# 18_ETH.net
KiCad netlist of a schematic drawn in Altium Designer
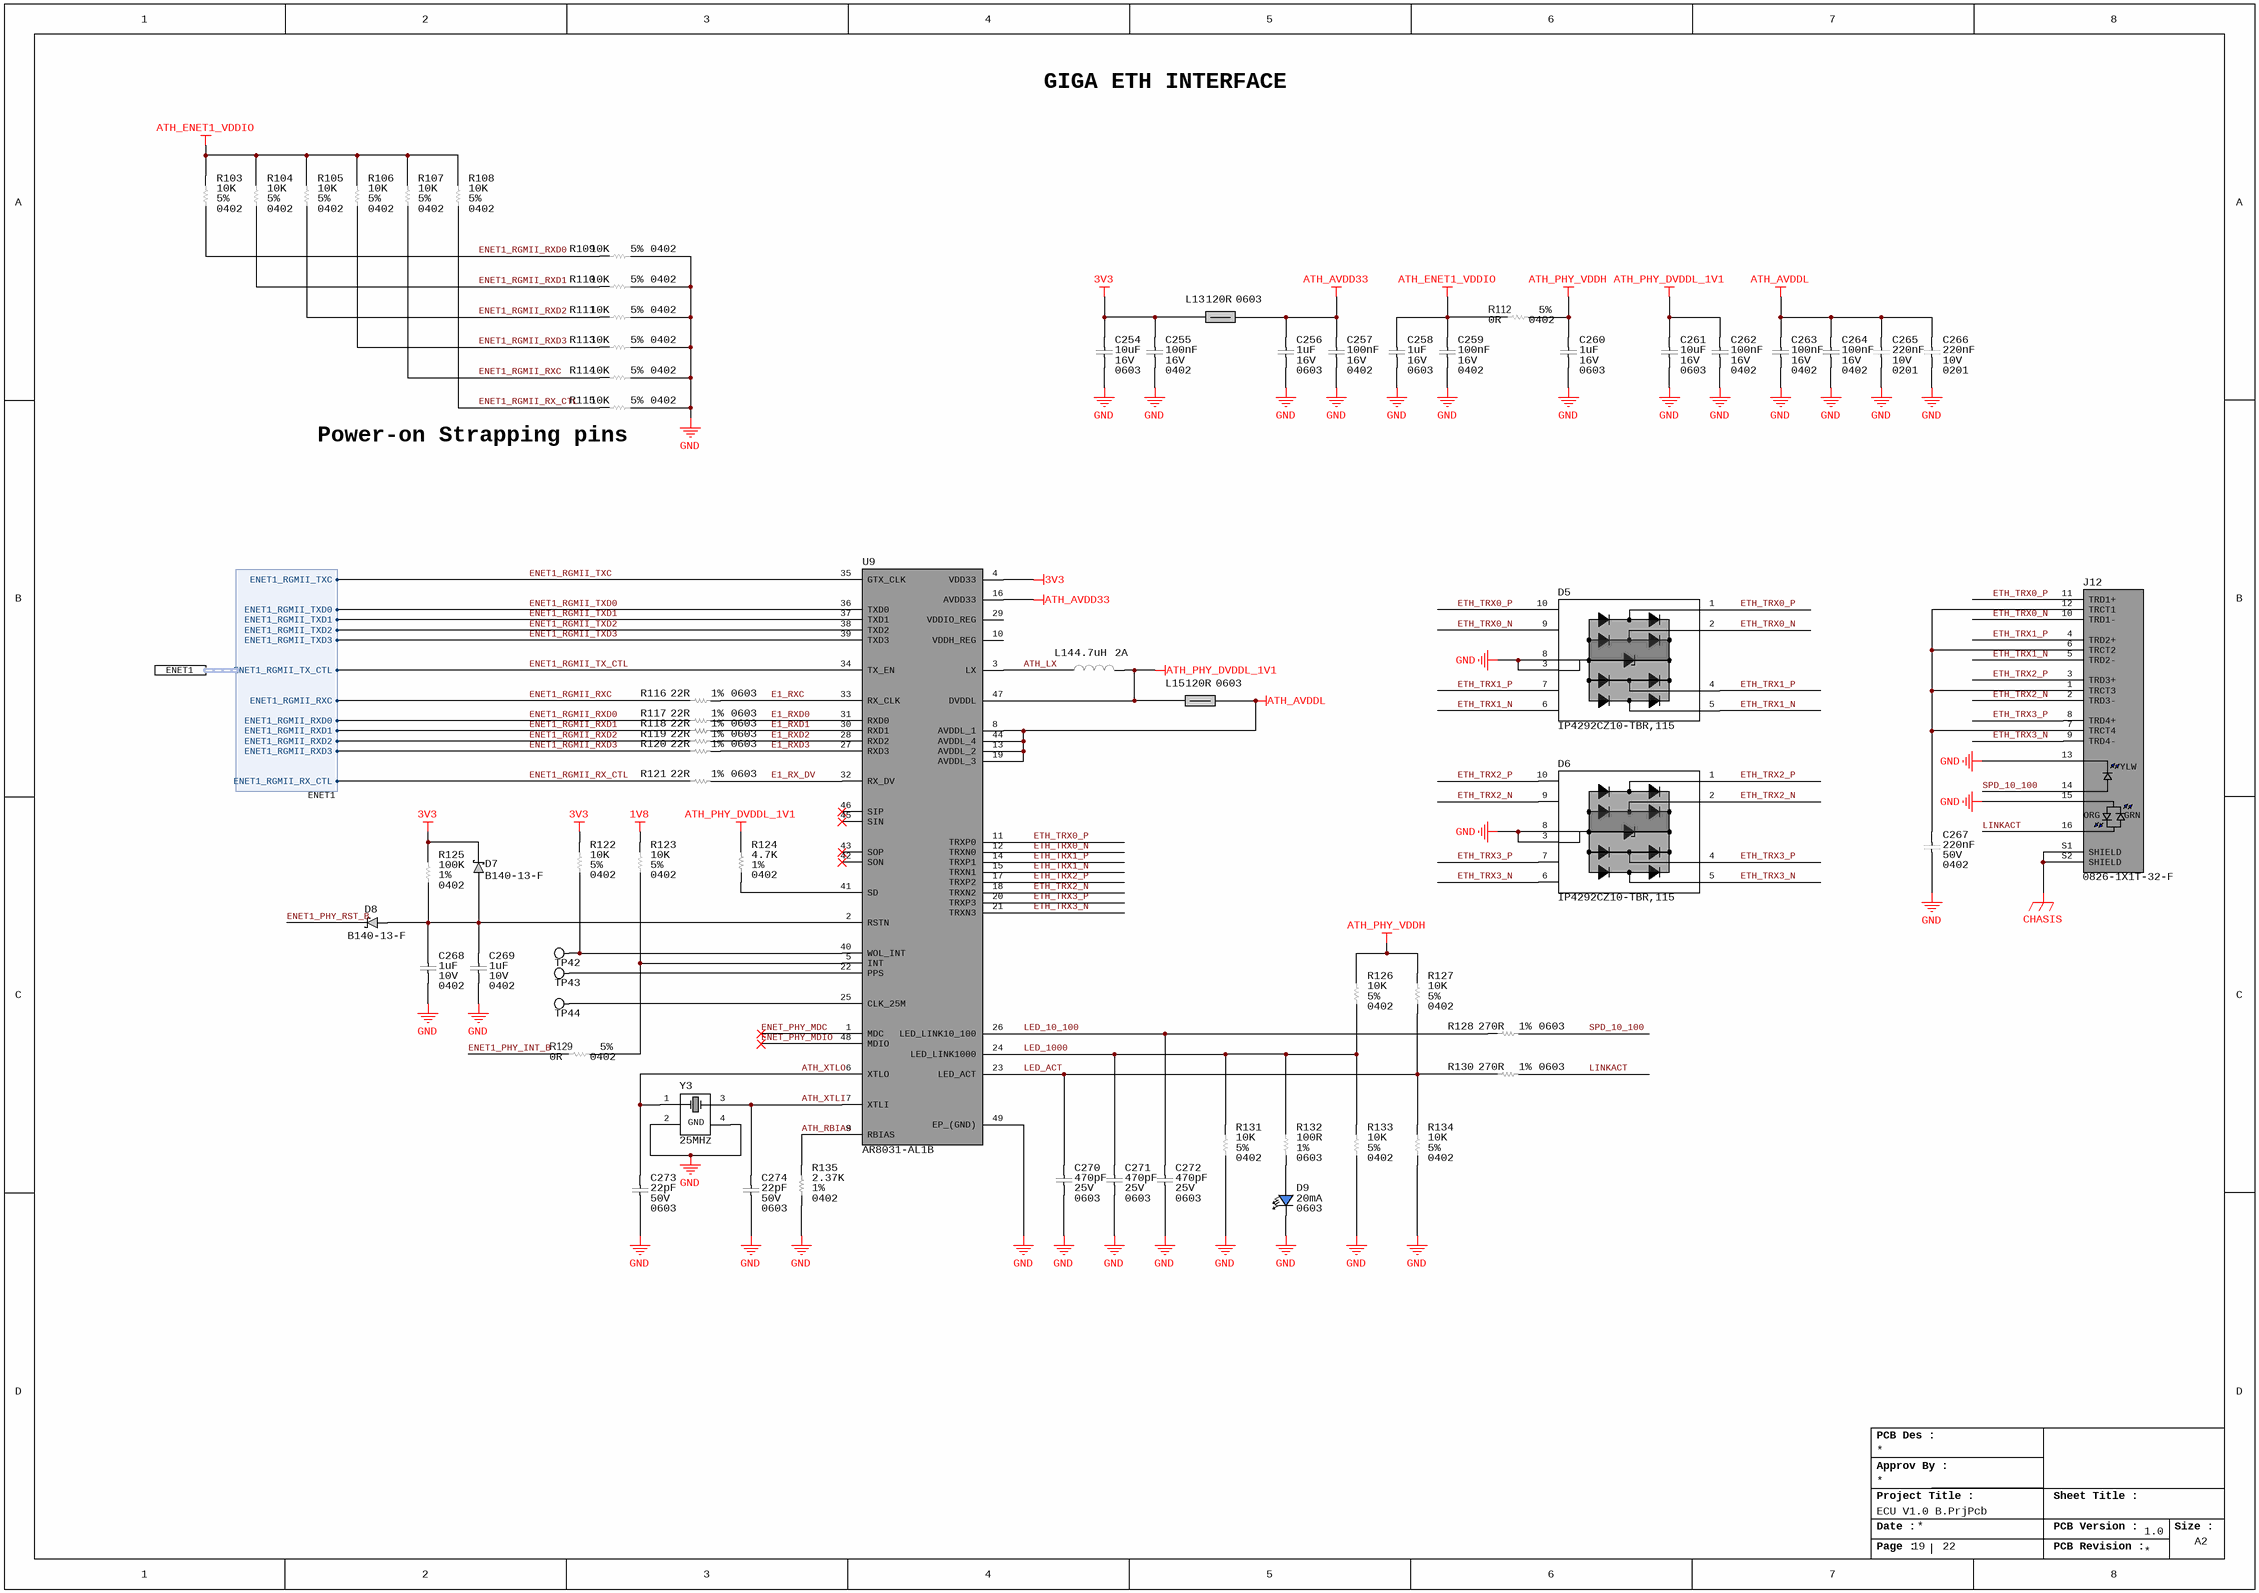
[diagram p0: 18_ETH.SchDoc]

(export (version "E")
  (design (tool "Eeschema 10.0.6"))
  (components
    (comp (ref "C254")
      (value "GRM188R61C106MAALD")
      (footprint "CAP_0603_CAPC1608X08N")
      (description "0603 10 uF 16 V ±20% Tolerance X5R Multilayer Ceramic Chip Capacitor")
      (fields
        (field (name "MANUFACTURER") "Murata")
        (field (name "TOLERANCE") "20%")
        (field (name "VOLTAGE RATING") "16V")
        (field (name "CAPACITANCE") "10uF")
        (field (name "CASE/PACKAGE") "0603")
      )
      (libsource (lib "Electronic Devices_LIB") (part "CAP_10UF_16V_X5R_0603"))
    )
    (comp (ref "C255")
      (value "CL05B104KO5NNNC")
      (footprint "CAP_0402_CAPC1005X05N")
      (description "Multilayer Ceramic Capacitor, 0.1 uF, 16 V, ± 10%, X7R, 0402 [1005 Metric]")
      (fields
        (field (name "MANUFACTURER") "Samsung")
        (field (name "TOLERANCE") "10%")
        (field (name "VOLTAGE RATING") "16V")
        (field (name "CAPACITANCE") "100nF")
        (field (name "CASE/PACKAGE") "0402")
      )
      (libsource (lib "Electronic Devices_LIB") (part "CAP_100NF_16V_X7R_0402"))
    )
    (comp (ref "C256")
      (value "CL10A105KO8NNNC")
      (footprint "CAP_0603_CAPC1608X08N")
      (description "CAP CER 1UF 16V X5R 0603")
      (fields
        (field (name "MANUFACTURER") "Samsung")
        (field (name "TOLERANCE") "10%")
        (field (name "VOLTAGE RATING") "16V")
        (field (name "CAPACITANCE") "1uF")
        (field (name "CASE/PACKAGE") "0603")
      )
      (libsource (lib "Electronic Devices_LIB") (part "CAP_1UF_16V_X5R_0603"))
    )
    (comp (ref "C257")
      (value "CL05B104KO5NNNC")
      (footprint "CAP_0402_CAPC1005X05N")
      (description "Multilayer Ceramic Capacitor, 0.1 uF, 16 V, ± 10%, X7R, 0402 [1005 Metric]")
      (fields
        (field (name "MANUFACTURER") "Samsung")
        (field (name "TOLERANCE") "10%")
        (field (name "VOLTAGE RATING") "16V")
        (field (name "CAPACITANCE") "100nF")
        (field (name "CASE/PACKAGE") "0402")
      )
      (libsource (lib "Electronic Devices_LIB") (part "CAP_100NF_16V_X7R_0402"))
    )
    (comp (ref "C258")
      (value "CL10A105KO8NNNC")
      (footprint "CAP_0603_CAPC1608X08N")
      (description "CAP CER 1UF 16V X5R 0603")
      (fields
        (field (name "MANUFACTURER") "Samsung")
        (field (name "TOLERANCE") "10%")
        (field (name "VOLTAGE RATING") "16V")
        (field (name "CAPACITANCE") "1uF")
        (field (name "CASE/PACKAGE") "0603")
      )
      (libsource (lib "Electronic Devices_LIB") (part "CAP_1UF_16V_X5R_0603"))
    )
    (comp (ref "C259")
      (value "CL05B104KO5NNNC")
      (footprint "CAP_0402_CAPC1005X05N")
      (description "Multilayer Ceramic Capacitor, 0.1 uF, 16 V, ± 10%, X7R, 0402 [1005 Metric]")
      (fields
        (field (name "MANUFACTURER") "Samsung")
        (field (name "TOLERANCE") "10%")
        (field (name "VOLTAGE RATING") "16V")
        (field (name "CAPACITANCE") "100nF")
        (field (name "CASE/PACKAGE") "0402")
      )
      (libsource (lib "Electronic Devices_LIB") (part "CAP_100NF_16V_X7R_0402"))
    )
    (comp (ref "C260")
      (value "CL10A105KO8NNNC")
      (footprint "CAP_0603_CAPC1608X08N")
      (description "CAP CER 1UF 16V X5R 0603")
      (fields
        (field (name "MANUFACTURER") "Samsung")
        (field (name "TOLERANCE") "10%")
        (field (name "VOLTAGE RATING") "16V")
        (field (name "CAPACITANCE") "1uF")
        (field (name "CASE/PACKAGE") "0603")
      )
      (libsource (lib "Electronic Devices_LIB") (part "CAP_1UF_16V_X5R_0603"))
    )
    (comp (ref "C261")
      (value "GRM188R61C106MAALD")
      (footprint "CAP_0603_CAPC1608X08N")
      (description "0603 10 uF 16 V ±20% Tolerance X5R Multilayer Ceramic Chip Capacitor")
      (fields
        (field (name "MANUFACTURER") "Murata")
        (field (name "TOLERANCE") "20%")
        (field (name "VOLTAGE RATING") "16V")
        (field (name "CAPACITANCE") "10uF")
        (field (name "CASE/PACKAGE") "0603")
      )
      (libsource (lib "Electronic Devices_LIB") (part "CAP_10UF_16V_X5R_0603"))
    )
    (comp (ref "C262")
      (value "CL05B104KO5NNNC")
      (footprint "CAP_0402_CAPC1005X05N")
      (description "Multilayer Ceramic Capacitor, 0.1 uF, 16 V, ± 10%, X7R, 0402 [1005 Metric]")
      (fields
        (field (name "MANUFACTURER") "Samsung")
        (field (name "TOLERANCE") "10%")
        (field (name "VOLTAGE RATING") "16V")
        (field (name "CAPACITANCE") "100nF")
        (field (name "CASE/PACKAGE") "0402")
      )
      (libsource (lib "Electronic Devices_LIB") (part "CAP_100NF_16V_X7R_0402"))
    )
    (comp (ref "C263")
      (value "CL05B104KO5NNNC")
      (footprint "CAP_0402_CAPC1005X05N")
      (description "Multilayer Ceramic Capacitor, 0.1 uF, 16 V, ± 10%, X7R, 0402 [1005 Metric]")
      (fields
        (field (name "MANUFACTURER") "Samsung")
        (field (name "TOLERANCE") "10%")
        (field (name "VOLTAGE RATING") "16V")
        (field (name "CAPACITANCE") "100nF")
        (field (name "CASE/PACKAGE") "0402")
      )
      (libsource (lib "Electronic Devices_LIB") (part "CAP_100NF_16V_X7R_0402"))
    )
    (comp (ref "C264")
      (value "CL05B104KO5NNNC")
      (footprint "CAP_0402_CAPC1005X05N")
      (description "Multilayer Ceramic Capacitor, 0.1 uF, 16 V, ± 10%, X7R, 0402 [1005 Metric]")
      (fields
        (field (name "MANUFACTURER") "Samsung")
        (field (name "TOLERANCE") "10%")
        (field (name "VOLTAGE RATING") "16V")
        (field (name "CAPACITANCE") "100nF")
        (field (name "CASE/PACKAGE") "0402")
      )
      (libsource (lib "Electronic Devices_LIB") (part "CAP_100NF_16V_X7R_0402"))
    )
    (comp (ref "C265")
      (value "LMK063BJ224MP-F")
      (footprint "CAP_0201_CAPC0603X03N")
      (description "Multilayer Ceramic Capacitors (High dielectric type), 10V, 0.22 uF, ± 20 %, 0201, X5R, RoHS")
      (fields
        (field (name "MANUFACTURER") "Taiyo Yuden")
        (field (name "TOLERANCE") "20%")
        (field (name "VOLTAGE RATING (DC)") "10V")
        (field (name "CAPACITANCE") "220nF")
        (field (name "CASE/PACKAGE") "0201")
      )
      (libsource (lib "Electronic Devices_LIB") (part "CAP_0.22UF_10V_X5R_0201"))
    )
    (comp (ref "C266")
      (value "LMK063BJ224MP-F")
      (footprint "CAP_0201_CAPC0603X03N")
      (description "Multilayer Ceramic Capacitors (High dielectric type), 10V, 0.22 uF, ± 20 %, 0201, X5R, RoHS")
      (fields
        (field (name "MANUFACTURER") "Taiyo Yuden")
        (field (name "TOLERANCE") "20%")
        (field (name "VOLTAGE RATING (DC)") "10V")
        (field (name "CAPACITANCE") "220nF")
        (field (name "CASE/PACKAGE") "0201")
      )
      (libsource (lib "Electronic Devices_LIB") (part "CAP_0.22UF_10V_X5R_0201"))
    )
    (comp (ref "C267")
      (value "GRM155R61H224KE01W")
      (footprint "CAP_0402_CAPC1005X05N")
      (description "Multilayer Ceramic Capacitor, 0.22 uF, 50 VDC, ± 10%, X5R, 0402 [1005 Metric]")
      (fields
        (field (name "MANUFACTURER") "Murata")
        (field (name "CASE/PACKAGE") "0402")
        (field (name "VOLTAGE RATING (DC)") "50V")
        (field (name "CAPACITANCE") "220nF")
      )
      (libsource (lib "Electronic Devices_LIB") (part "CAP_0.22UF_50V_X5R_0402"))
    )
    (comp (ref "C268")
      (value "GRM155C81A105KA12D")
      (footprint "CAP_0402_CAPC1005X05N")
      (description "0402 10 V 1 uF ±10% Tolerance X6S Multilayer Ceramic Capacitor")
      (fields
        (field (name "MANUFACTURER") "Murata")
        (field (name "TOLERANCE") "10%")
        (field (name "VOLTAGE RATING") "10V")
        (field (name "CAPACITANCE") "1uF")
        (field (name "CASE/PACKAGE") "0402")
      )
      (libsource (lib "Electronic Devices_LIB") (part "CAP_1UF_10V_X6S_0402"))
    )
    (comp (ref "C269")
      (value "GRM155C81A105KA12D")
      (footprint "CAP_0402_CAPC1005X05N")
      (description "0402 10 V 1 uF ±10% Tolerance X6S Multilayer Ceramic Capacitor")
      (fields
        (field (name "MANUFACTURER") "Murata")
        (field (name "TOLERANCE") "10%")
        (field (name "VOLTAGE RATING") "10V")
        (field (name "CAPACITANCE") "1uF")
        (field (name "CASE/PACKAGE") "0402")
      )
      (libsource (lib "Electronic Devices_LIB") (part "CAP_1UF_10V_X6S_0402"))
    )
    (comp (ref "C270")
      (value "C0603C471K3RACTU")
      (footprint "CAP_0603_CAPC1608X08N")
      (fields
        (field (name "MANUFACTURER") "KEMET")
        (field (name "TOLERANCE") "10%")
        (field (name "VOLTAGE RATING") "25V")
        (field (name "CAPACITANCE") "470pF")
        (field (name "CASE CODE (IMPERIAL)") "0603")
      )
      (libsource (lib "Electronic Devices_LIB") (part "CAP_470pF_25V_X7R_0603"))
    )
    (comp (ref "C271")
      (value "C0603C471K3RACTU")
      (footprint "CAP_0603_CAPC1608X08N")
      (fields
        (field (name "MANUFACTURER") "KEMET")
        (field (name "TOLERANCE") "10%")
        (field (name "VOLTAGE RATING") "25V")
        (field (name "CAPACITANCE") "470pF")
        (field (name "CASE CODE (IMPERIAL)") "0603")
      )
      (libsource (lib "Electronic Devices_LIB") (part "CAP_470pF_25V_X7R_0603"))
    )
    (comp (ref "C272")
      (value "C0603C471K3RACTU")
      (footprint "CAP_0603_CAPC1608X08N")
      (fields
        (field (name "MANUFACTURER") "KEMET")
        (field (name "TOLERANCE") "10%")
        (field (name "VOLTAGE RATING") "25V")
        (field (name "CAPACITANCE") "470pF")
        (field (name "CASE CODE (IMPERIAL)") "0603")
      )
      (libsource (lib "Electronic Devices_LIB") (part "CAP_470pF_25V_X7R_0603"))
    )
    (comp (ref "C273")
      (value "C0603C220J5GACTU")
      (footprint "CAP_0603_CAPC1608X08N")
      (description "Multilayer Ceramic Capacitor, 22 pF, 50 V, ï¿½ 5%, C0G (NP0), 0603 [1608 Metric]")
      (fields
        (field (name "MANUFACTURER") "KEMET")
        (field (name "TOLERANCE") "5%")
        (field (name "VOLTAGE RATING (DC)") "50V")
        (field (name "CAPACITANCE") "22pF")
        (field (name "CASE/PACKAGE") "0603")
      )
      (libsource (lib "Electronic Devices_LIB") (part "CAP_22pF_50V_NP0_0603"))
    )
    (comp (ref "C274")
      (value "C0603C220J5GACTU")
      (footprint "CAP_0603_CAPC1608X08N")
      (description "Multilayer Ceramic Capacitor, 22 pF, 50 V, ï¿½ 5%, C0G (NP0), 0603 [1608 Metric]")
      (fields
        (field (name "MANUFACTURER") "KEMET")
        (field (name "TOLERANCE") "5%")
        (field (name "VOLTAGE RATING (DC)") "50V")
        (field (name "CAPACITANCE") "22pF")
        (field (name "CASE/PACKAGE") "0603")
      )
      (libsource (lib "Electronic Devices_LIB") (part "CAP_22pF_50V_NP0_0603"))
    )
    (comp (ref "D5")
      (value "IP4292CZ10-TBR,115")
      (footprint "DIO_TVS_SON50P100X250X50-10N")
      (description "IP4292CZ10 Series 4 Channel 4 V 0.55 pF ESD Protected TVS Diode - DFN2510A-10")
      (fields (field (name "MANUFACTURER") "Nexperia"))
      (libsource (lib "Electronic Devices_LIB") (part "DIO_TVS_4CH_4V_IP4292CZ10-TBR,115"))
    )
    (comp (ref "D6")
      (value "IP4292CZ10-TBR,115")
      (footprint "DIO_TVS_SON50P100X250X50-10N")
      (description "IP4292CZ10 Series 4 Channel 4 V 0.55 pF ESD Protected TVS Diode - DFN2510A-10")
      (fields (field (name "MANUFACTURER") "Nexperia"))
      (libsource (lib "Electronic Devices_LIB") (part "DIO_TVS_4CH_4V_IP4292CZ10-TBR,115"))
    )
    (comp (ref "D7")
      (value "B140-13-F")
      (footprint "DIOM5226X240N")
      (description "Rectifier Diode, Schottky, 1 Phase, 1 Element, 1A, 40V V(RRM), Silicon, DO-214AC")
      (fields (field (name "MANUFACTURER") "Diodes"))
      (libsource (lib "Electronic Devices_LIB") (part "DIO_SCTKY_40V_1A_B140-13-F"))
    )
    (comp (ref "D8")
      (value "B140-13-F")
      (footprint "DIOM5226X240N")
      (description "Rectifier Diode, Schottky, 1 Phase, 1 Element, 1A, 40V V(RRM), Silicon, DO-214AC")
      (fields (field (name "MANUFACTURER") "Diodes"))
      (libsource (lib "Electronic Devices_LIB") (part "DIO_SCTKY_40V_1A_B140-13-F"))
    )
    (comp (ref "D9")
      (value "ASCKCB00-NS3T4010302")
      (footprint "LED_0603-BLUE-0.75mm")
      (description "LED Single Chip Blue 467nm 20mA 2-Pin DFN T/R")
      (fields
        (field (name "MANUFACTURER") "Broadcom")
        (field (name "CASE/PACKCAGE") "0603")
        (field (name "TEST CURRENT") "20mA")
      )
      (libsource (lib "Electronic Devices_LIB") (part "LED_DIO_BLUE_20mA_0603_ASCKCB00-NS3T4010302"))
    )
    (comp (ref "J12")
      (value "0826-1X1T-32-F")
      (footprint "BEL_0826-1X1T-32-F")
      (description "Modular Connectors / Ethernet Connectors RJ45 Connector")
      (fields (field (name "MANUFACTURER") "Bel"))
      (libsource (lib "Electronic Devices_LIB") (part "CONN_RJ45_0826-1X1T-32-F"))
    )
    (comp (ref "L13")
      (value "BLM18PG121SH1D")
      (footprint "IND_0603_INDC1608X08N")
      (description "Ferrite Beads Multi-Layer 120Ohm 25% 100MHz 2A 50mOhm DCR 0603 Automotive Paper T/R")
      (fields
        (field (name "MANUFACTURER") "Murata")
        (field (name "TOLERANCE") "25%")
        (field (name "IMPEDANCE") "120R")
        (field (name "CASE/PACKAGE") "0603")
      )
      (libsource (lib "Electronic Devices_LIB") (part "IND_FERRITE_BEADS_120R_2A_0603_BLM18PG121SH1D"))
    )
    (comp (ref "L14")
      (value "DFE252012P-4R7M=P2")
      (footprint "DFE2HCAH1R0MJ0L")
      (description "Inductor Power Shielded Wirewound 4.7uH 20% 1MHz Metal 1.4A 0.2Ohm DCR 1008 T/R")
      (fields
        (field (name "MANUFACTURER") "Murata")
        (field (name "TOLERANCE") "20%")
        (field (name "CURRENT RATING") "2A")
        (field (name "INDUCTANCE") "4.7uH")
      )
      (libsource (lib "Electronic Devices_LIB") (part "IND_4.7uF_1.4A-DFE252012P-4R7M=P2"))
    )
    (comp (ref "L15")
      (value "BLM18PG121SH1D")
      (footprint "IND_0603_INDC1608X08N")
      (description "Ferrite Beads Multi-Layer 120Ohm 25% 100MHz 2A 50mOhm DCR 0603 Automotive Paper T/R")
      (fields
        (field (name "MANUFACTURER") "Murata")
        (field (name "TOLERANCE") "25%")
        (field (name "IMPEDANCE") "120R")
        (field (name "CASE/PACKAGE") "0603")
      )
      (libsource (lib "Electronic Devices_LIB") (part "IND_FERRITE_BEADS_120R_2A_0603_BLM18PG121SH1D"))
    )
    (comp (ref "R103")
      (value "ERJ-2GEJ103X")
      (footprint "RES_0402_RESC1005X04N")
      (description "Res Thick Film 0402 10K Ohm 5% 1/10W ±200ppm/°C Molded SMD Punched Carrier T/R")
      (fields
        (field (name "MANUFACTURER") "Panasonic")
        (field (name "TOLERANCE") "5%")
        (field (name "RESISTANCE") "10K")
        (field (name "CASE/PACKAGE") "0402")
      )
      (libsource (lib "Electronic Devices_LIB") (part "RES_10K_5%_100mW_0402"))
    )
    (comp (ref "R104")
      (value "ERJ-2GEJ103X")
      (footprint "RES_0402_RESC1005X04N")
      (description "Res Thick Film 0402 10K Ohm 5% 1/10W ±200ppm/°C Molded SMD Punched Carrier T/R")
      (fields
        (field (name "MANUFACTURER") "Panasonic")
        (field (name "TOLERANCE") "5%")
        (field (name "RESISTANCE") "10K")
        (field (name "CASE/PACKAGE") "0402")
      )
      (libsource (lib "Electronic Devices_LIB") (part "RES_10K_5%_100mW_0402"))
    )
    (comp (ref "R105")
      (value "ERJ-2GEJ103X")
      (footprint "RES_0402_RESC1005X04N")
      (description "Res Thick Film 0402 10K Ohm 5% 1/10W ±200ppm/°C Molded SMD Punched Carrier T/R")
      (fields
        (field (name "MANUFACTURER") "Panasonic")
        (field (name "TOLERANCE") "5%")
        (field (name "RESISTANCE") "10K")
        (field (name "CASE/PACKAGE") "0402")
      )
      (libsource (lib "Electronic Devices_LIB") (part "RES_10K_5%_100mW_0402"))
    )
    (comp (ref "R106")
      (value "ERJ-2GEJ103X")
      (footprint "RES_0402_RESC1005X04N")
      (description "Res Thick Film 0402 10K Ohm 5% 1/10W ±200ppm/°C Molded SMD Punched Carrier T/R")
      (fields
        (field (name "MANUFACTURER") "Panasonic")
        (field (name "TOLERANCE") "5%")
        (field (name "RESISTANCE") "10K")
        (field (name "CASE/PACKAGE") "0402")
      )
      (libsource (lib "Electronic Devices_LIB") (part "RES_10K_5%_100mW_0402"))
    )
    (comp (ref "R107")
      (value "ERJ-2GEJ103X")
      (footprint "RES_0402_RESC1005X04N")
      (description "Res Thick Film 0402 10K Ohm 5% 1/10W ±200ppm/°C Molded SMD Punched Carrier T/R")
      (fields
        (field (name "MANUFACTURER") "Panasonic")
        (field (name "TOLERANCE") "5%")
        (field (name "RESISTANCE") "10K")
        (field (name "CASE/PACKAGE") "0402")
      )
      (libsource (lib "Electronic Devices_LIB") (part "RES_10K_5%_100mW_0402"))
    )
    (comp (ref "R108")
      (value "ERJ-2GEJ103X")
      (footprint "RES_0402_RESC1005X04N")
      (description "Res Thick Film 0402 10K Ohm 5% 1/10W ±200ppm/°C Molded SMD Punched Carrier T/R")
      (fields
        (field (name "MANUFACTURER") "Panasonic")
        (field (name "TOLERANCE") "5%")
        (field (name "RESISTANCE") "10K")
        (field (name "CASE/PACKAGE") "0402")
      )
      (libsource (lib "Electronic Devices_LIB") (part "RES_10K_5%_100mW_0402"))
    )
    (comp (ref "R109")
      (value "ERJ-2GEJ103X")
      (footprint "RES_0402_RESC1005X04N")
      (description "Res Thick Film 0402 10K Ohm 5% 1/10W ±200ppm/°C Molded SMD Punched Carrier T/R")
      (fields
        (field (name "MANUFACTURER") "Panasonic")
        (field (name "TOLERANCE") "5%")
        (field (name "RESISTANCE") "10K")
        (field (name "CASE/PACKAGE") "0402")
      )
      (libsource (lib "Electronic Devices_LIB") (part "RES_10K_5%_100mW_0402"))
    )
    (comp (ref "R110")
      (value "ERJ-2GEJ103X")
      (footprint "RES_0402_RESC1005X04N")
      (description "Res Thick Film 0402 10K Ohm 5% 1/10W ±200ppm/°C Molded SMD Punched Carrier T/R")
      (fields
        (field (name "MANUFACTURER") "Panasonic")
        (field (name "TOLERANCE") "5%")
        (field (name "RESISTANCE") "10K")
        (field (name "CASE/PACKAGE") "0402")
      )
      (libsource (lib "Electronic Devices_LIB") (part "RES_10K_5%_100mW_0402"))
    )
    (comp (ref "R111")
      (value "ERJ-2GEJ103X")
      (footprint "RES_0402_RESC1005X04N")
      (description "Res Thick Film 0402 10K Ohm 5% 1/10W ±200ppm/°C Molded SMD Punched Carrier T/R")
      (fields
        (field (name "MANUFACTURER") "Panasonic")
        (field (name "TOLERANCE") "5%")
        (field (name "RESISTANCE") "10K")
        (field (name "CASE/PACKAGE") "0402")
      )
      (libsource (lib "Electronic Devices_LIB") (part "RES_10K_5%_100mW_0402"))
    )
    (comp (ref "R112")
      (value "ERJ-2GE0R00X")
      (footprint "RES_0402_RESC1005X04N")
      (description "SMD Chip Resistor, Jumper, 0 ohm, 100 mW, 0402 [1005 Metric], Thick Film, General Purpose")
      (fields
        (field (name "MANUFACTURER") "Panasonic")
        (field (name "CASE CODE (IMPERIAL)") "0402")
        (field (name "TOLERANCE") "5%")
        (field (name "RESISTANCE") "0R")
      )
      (libsource (lib "Electronic Devices_LIB") (part "RES_0R_5%_100mW_0402"))
    )
    (comp (ref "R113")
      (value "ERJ-2GEJ103X")
      (footprint "RES_0402_RESC1005X04N")
      (description "Res Thick Film 0402 10K Ohm 5% 1/10W ±200ppm/°C Molded SMD Punched Carrier T/R")
      (fields
        (field (name "MANUFACTURER") "Panasonic")
        (field (name "TOLERANCE") "5%")
        (field (name "RESISTANCE") "10K")
        (field (name "CASE/PACKAGE") "0402")
      )
      (libsource (lib "Electronic Devices_LIB") (part "RES_10K_5%_100mW_0402"))
    )
    (comp (ref "R114")
      (value "ERJ-2GEJ103X")
      (footprint "RES_0402_RESC1005X04N")
      (description "Res Thick Film 0402 10K Ohm 5% 1/10W ±200ppm/°C Molded SMD Punched Carrier T/R")
      (fields
        (field (name "MANUFACTURER") "Panasonic")
        (field (name "TOLERANCE") "5%")
        (field (name "RESISTANCE") "10K")
        (field (name "CASE/PACKAGE") "0402")
      )
      (libsource (lib "Electronic Devices_LIB") (part "RES_10K_5%_100mW_0402"))
    )
    (comp (ref "R115")
      (value "ERJ-2GEJ103X")
      (footprint "RES_0402_RESC1005X04N")
      (description "Res Thick Film 0402 10K Ohm 5% 1/10W ±200ppm/°C Molded SMD Punched Carrier T/R")
      (fields
        (field (name "MANUFACTURER") "Panasonic")
        (field (name "TOLERANCE") "5%")
        (field (name "RESISTANCE") "10K")
        (field (name "CASE/PACKAGE") "0402")
      )
      (libsource (lib "Electronic Devices_LIB") (part "RES_10K_5%_100mW_0402"))
    )
    (comp (ref "R116")
      (value "RC0603FR-0722RL")
      (footprint "RES_0603_RESC1608X04N")
      (description "Res Thick Film 0603 22 Ohm 1% 0.1W(1/10W) ±100ppm/C Pad SMD T/R")
      (fields
        (field (name "MANUFACTURER") "Yageo")
        (field (name "TOLERANCE") "1%")
        (field (name "RESISTANCE") "22R")
        (field (name "CASE/PACKAGE") "0603")
      )
      (libsource (lib "Electronic Devices_LIB") (part "RES_22R_1%_100mW_0603"))
    )
    (comp (ref "R117")
      (value "RC0603FR-0722RL")
      (footprint "RES_0603_RESC1608X04N")
      (description "Res Thick Film 0603 22 Ohm 1% 0.1W(1/10W) ±100ppm/C Pad SMD T/R")
      (fields
        (field (name "MANUFACTURER") "Yageo")
        (field (name "TOLERANCE") "1%")
        (field (name "RESISTANCE") "22R")
        (field (name "CASE/PACKAGE") "0603")
      )
      (libsource (lib "Electronic Devices_LIB") (part "RES_22R_1%_100mW_0603"))
    )
    (comp (ref "R118")
      (value "RC0603FR-0722RL")
      (footprint "RES_0603_RESC1608X04N")
      (description "Res Thick Film 0603 22 Ohm 1% 0.1W(1/10W) ±100ppm/C Pad SMD T/R")
      (fields
        (field (name "MANUFACTURER") "Yageo")
        (field (name "TOLERANCE") "1%")
        (field (name "RESISTANCE") "22R")
        (field (name "CASE/PACKAGE") "0603")
      )
      (libsource (lib "Electronic Devices_LIB") (part "RES_22R_1%_100mW_0603"))
    )
    (comp (ref "R119")
      (value "RC0603FR-0722RL")
      (footprint "RES_0603_RESC1608X04N")
      (description "Res Thick Film 0603 22 Ohm 1% 0.1W(1/10W) ±100ppm/C Pad SMD T/R")
      (fields
        (field (name "MANUFACTURER") "Yageo")
        (field (name "TOLERANCE") "1%")
        (field (name "RESISTANCE") "22R")
        (field (name "CASE/PACKAGE") "0603")
      )
      (libsource (lib "Electronic Devices_LIB") (part "RES_22R_1%_100mW_0603"))
    )
    (comp (ref "R120")
      (value "RC0603FR-0722RL")
      (footprint "RES_0603_RESC1608X04N")
      (description "Res Thick Film 0603 22 Ohm 1% 0.1W(1/10W) ±100ppm/C Pad SMD T/R")
      (fields
        (field (name "MANUFACTURER") "Yageo")
        (field (name "TOLERANCE") "1%")
        (field (name "RESISTANCE") "22R")
        (field (name "CASE/PACKAGE") "0603")
      )
      (libsource (lib "Electronic Devices_LIB") (part "RES_22R_1%_100mW_0603"))
    )
    (comp (ref "R121")
      (value "RC0603FR-0722RL")
      (footprint "RES_0603_RESC1608X04N")
      (description "Res Thick Film 0603 22 Ohm 1% 0.1W(1/10W) ±100ppm/C Pad SMD T/R")
      (fields
        (field (name "MANUFACTURER") "Yageo")
        (field (name "TOLERANCE") "1%")
        (field (name "RESISTANCE") "22R")
        (field (name "CASE/PACKAGE") "0603")
      )
      (libsource (lib "Electronic Devices_LIB") (part "RES_22R_1%_100mW_0603"))
    )
    (comp (ref "R122")
      (value "ERJ-2GEJ103X")
      (footprint "RES_0402_RESC1005X04N")
      (description "Res Thick Film 0402 10K Ohm 5% 1/10W ±200ppm/°C Molded SMD Punched Carrier T/R")
      (fields
        (field (name "MANUFACTURER") "Panasonic")
        (field (name "TOLERANCE") "5%")
        (field (name "RESISTANCE") "10K")
        (field (name "CASE/PACKAGE") "0402")
      )
      (libsource (lib "Electronic Devices_LIB") (part "RES_10K_5%_100mW_0402"))
    )
    (comp (ref "R123")
      (value "ERJ-2GEJ103X")
      (footprint "RES_0402_RESC1005X04N")
      (description "Res Thick Film 0402 10K Ohm 5% 1/10W ±200ppm/°C Molded SMD Punched Carrier T/R")
      (fields
        (field (name "MANUFACTURER") "Panasonic")
        (field (name "TOLERANCE") "5%")
        (field (name "RESISTANCE") "10K")
        (field (name "CASE/PACKAGE") "0402")
      )
      (libsource (lib "Electronic Devices_LIB") (part "RES_10K_5%_100mW_0402"))
    )
    (comp (ref "R124")
      (value "ERJ-2RKF4701X")
      (footprint "RES_0402_RESC1005X04N")
      (description "Res Thick Film 0402 4.7K Ohm 1% 0.1W ±100ppm/°C Molded SMD Punched Carrier T/R")
      (fields
        (field (name "MANUFACTURER") "Panasonic")
        (field (name "TOLERANCE") "1%")
        (field (name "CASE CODE (IMPERIAL)") "0402")
        (field (name "RESISTANCE") "4.7K")
      )
      (libsource (lib "Electronic Devices_LIB") (part "RES_4.7K_1%_100mW_0402"))
    )
    (comp (ref "R125")
      (value "RC0402FR-07100KL")
      (footprint "RES_0402_RESC1005X04N")
      (description "SMD Chip Resistor, 100 kOhm, ± 1%, 63 mW, 0402 [1005 Metric], Thick Film, General Purpose")
      (fields
        (field (name "MANUFACTURER") "Yageo")
        (field (name "RESISTANCE") "100K")
        (field (name "TOLERANCE") "1%")
        (field (name "CASE/PACKAGE") "0402")
      )
      (libsource (lib "Electronic Devices_LIB") (part "RES_100K_1%_100mW_0402"))
    )
    (comp (ref "R126")
      (value "ERJ-2GEJ103X")
      (footprint "RES_0402_RESC1005X04N")
      (description "Res Thick Film 0402 10K Ohm 5% 1/10W ±200ppm/°C Molded SMD Punched Carrier T/R")
      (fields
        (field (name "MANUFACTURER") "Panasonic")
        (field (name "TOLERANCE") "5%")
        (field (name "RESISTANCE") "10K")
        (field (name "CASE/PACKAGE") "0402")
      )
      (libsource (lib "Electronic Devices_LIB") (part "RES_10K_5%_100mW_0402"))
    )
    (comp (ref "R127")
      (value "ERJ-2GEJ103X")
      (footprint "RES_0402_RESC1005X04N")
      (description "Res Thick Film 0402 10K Ohm 5% 1/10W ±200ppm/°C Molded SMD Punched Carrier T/R")
      (fields
        (field (name "MANUFACTURER") "Panasonic")
        (field (name "TOLERANCE") "5%")
        (field (name "RESISTANCE") "10K")
        (field (name "CASE/PACKAGE") "0402")
      )
      (libsource (lib "Electronic Devices_LIB") (part "RES_10K_5%_100mW_0402"))
    )
    (comp (ref "R128")
      (value "RC0603FR-07270RL")
      (footprint "RES_0603_RESC1608X04N")
      (description "SMD Chip Resistor, 270 Ohm, ï¿½ 1%, 100 mW, 0603 [1608 Metric], Thick Film, General Purpose")
      (fields
        (field (name "MANUFACTURER") "Yageo")
        (field (name "TOLERANCE") "1%")
        (field (name "RESISTANCE") "270R")
        (field (name "CASE/PACKAGE") "0603")
      )
      (libsource (lib "Electronic Devices_LIB") (part "RES_270R_1%_100mW_0603"))
    )
    (comp (ref "R129")
      (value "ERJ-2GE0R00X")
      (footprint "RES_0402_RESC1005X04N")
      (description "SMD Chip Resistor, Jumper, 0 ohm, 100 mW, 0402 [1005 Metric], Thick Film, General Purpose")
      (fields
        (field (name "MANUFACTURER") "Panasonic")
        (field (name "CASE CODE (IMPERIAL)") "0402")
        (field (name "TOLERANCE") "5%")
        (field (name "RESISTANCE") "0R")
      )
      (libsource (lib "Electronic Devices_LIB") (part "RES_0R_5%_100mW_0402"))
    )
    (comp (ref "R130")
      (value "RC0603FR-07270RL")
      (footprint "RES_0603_RESC1608X04N")
      (description "SMD Chip Resistor, 270 Ohm, ï¿½ 1%, 100 mW, 0603 [1608 Metric], Thick Film, General Purpose")
      (fields
        (field (name "MANUFACTURER") "Yageo")
        (field (name "TOLERANCE") "1%")
        (field (name "RESISTANCE") "270R")
        (field (name "CASE/PACKAGE") "0603")
      )
      (libsource (lib "Electronic Devices_LIB") (part "RES_270R_1%_100mW_0603"))
    )
    (comp (ref "R131")
      (value "ERJ-2GEJ103X")
      (footprint "RES_0402_RESC1005X04N")
      (description "Res Thick Film 0402 10K Ohm 5% 1/10W ±200ppm/°C Molded SMD Punched Carrier T/R")
      (fields
        (field (name "MANUFACTURER") "Panasonic")
        (field (name "TOLERANCE") "5%")
        (field (name "RESISTANCE") "10K")
        (field (name "CASE/PACKAGE") "0402")
      )
      (libsource (lib "Electronic Devices_LIB") (part "RES_10K_5%_100mW_0402"))
    )
    (comp (ref "R132")
      (value "ERJ3EKF1000V")
      (footprint "CAP_0603_CAPC1608X08N")
      (description "Res Thick Film 0603 100 Ohm 1% 1/10W ±100ppm/°C Molded SMD Punched Carrier T/R")
      (fields
        (field (name "MANUFACTURER") "Panasonic")
        (field (name "CASE CODE (IMPERIAL)") "0603")
        (field (name "TOLERANCE") "1%")
        (field (name "RESISTANCE") "100R")
      )
      (libsource (lib "Electronic Devices_LIB") (part "RES_100R_1%_100MW_0603"))
    )
    (comp (ref "R133")
      (value "ERJ-2GEJ103X")
      (footprint "RES_0402_RESC1005X04N")
      (description "Res Thick Film 0402 10K Ohm 5% 1/10W ±200ppm/°C Molded SMD Punched Carrier T/R")
      (fields
        (field (name "MANUFACTURER") "Panasonic")
        (field (name "TOLERANCE") "5%")
        (field (name "RESISTANCE") "10K")
        (field (name "CASE/PACKAGE") "0402")
      )
      (libsource (lib "Electronic Devices_LIB") (part "RES_10K_5%_100mW_0402"))
    )
    (comp (ref "R134")
      (value "ERJ-2GEJ103X")
      (footprint "RES_0402_RESC1005X04N")
      (description "Res Thick Film 0402 10K Ohm 5% 1/10W ±200ppm/°C Molded SMD Punched Carrier T/R")
      (fields
        (field (name "MANUFACTURER") "Panasonic")
        (field (name "TOLERANCE") "5%")
        (field (name "RESISTANCE") "10K")
        (field (name "CASE/PACKAGE") "0402")
      )
      (libsource (lib "Electronic Devices_LIB") (part "RES_10K_5%_100mW_0402"))
    )
    (comp (ref "R135")
      (value "ERJ-2RKF2371X")
      (footprint "RES_0402_RESC1005X04N")
      (description "Res Thick Film 0402 2.37K Ohm 1% 1/10W ±100ppm/°C Molded SMD Punched Carrier T/R")
      (fields
        (field (name "MANUFACTURER") "Panasonic")
        (field (name "TOLERANCE") "1%")
        (field (name "RESISTANCE") "2.37K")
        (field (name "CASE/PACKAGE") "0402")
      )
      (libsource (lib "Electronic Devices_LIB") (part "RES_2.37K_1%_100mW_0402"))
    )
    (comp (ref "TP42")
      (value "NO COMPONENT")
      (footprint "TP_PAD_0.5MM_SMD_ROUND")
      (description "Test Point, SMD pad, round, 1.5mm, 1.6mm, 3mm diameter")
      (libsource (lib "Electronic Devices_LIB") (part "TP_PAD_SMD_SMALL"))
    )
    (comp (ref "TP43")
      (value "NO COMPONENT")
      (footprint "TP_PAD_0.5MM_SMD_ROUND")
      (description "Test Point, SMD pad, round, 1.5mm, 1.6mm, 3mm diameter")
      (libsource (lib "Electronic Devices_LIB") (part "TP_PAD_SMD_SMALL"))
    )
    (comp (ref "TP44")
      (value "NO COMPONENT")
      (footprint "TP_PAD_0.5MM_SMD_ROUND")
      (description "Test Point, SMD pad, round, 1.5mm, 1.6mm, 3mm diameter")
      (libsource (lib "Electronic Devices_LIB") (part "TP_PAD_SMD_SMALL"))
    )
    (comp (ref "U9")
      (value "AR8031-AL1B")
      (footprint "QFN40P600X600X80-49N")
      (description "IC TRANSCEIVER ETHERNET 48-QFN / PHY 10Mbps/100Mbps/1Gbps 3.3V 48-Pin QFN EP Tray")
      (fields (field (name "MANUFACTURER") "Qualcomm"))
      (libsource (lib "Electronic Devices_LIB") (part "IC_TRANSCEIVER_ETH_AR8031-AL1B"))
    )
    (comp (ref "Y3")
      (value "405C35B25M00000")
      (footprint "405C35B25M00000")
      (description "405 Series 25 MHz ±30 ppm 13 pF -20 to +70 °C Surface Mount Quartz Crystal")
      (fields
        (field (name "MANUFACTURER") "CTS")
        (field (name "FREQUENCY") "25MHz")
        (field (name "TOLERANCE") "30ppm")
      )
      (libsource (lib "Electronic Devices_LIB") (part "CRYSTAL_25MHZ_13PF_405C35B25M00000"))
    )
  )
  (nets
    (net (code "2") (name "/ATH_LX") (class "Default")
      (node (ref "L14") (pin "1") (pinfunction "1_1") (pintype "passive"))
      (node (ref "U9") (pin "3") (pinfunction "LX_3") (pintype "passive"))
    )
    (net (code "3") (name "/ATH_RBIAS") (class "Default")
      (node (ref "R135") (pin "2") (pinfunction "2_2") (pintype "passive"))
      (node (ref "U9") (pin "9") (pinfunction "RBIAS_9") (pintype "passive"))
    )
    (net (code "4") (name "/ATH_XTLI") (class "Default")
      (node (ref "C274") (pin "2") (pinfunction "2_2") (pintype "passive"))
      (node (ref "U9") (pin "7") (pinfunction "XTLI_7") (pintype "passive"))
      (node (ref "Y3") (pin "3") (pinfunction "XTAL_2_3") (pintype "passive"))
    )
    (net (code "5") (name "/ATH_XTLO") (class "Default")
      (node (ref "C273") (pin "2") (pinfunction "2_2") (pintype "passive"))
      (node (ref "U9") (pin "6") (pinfunction "XTLO_6") (pintype "passive"))
      (node (ref "Y3") (pin "1") (pinfunction "XTAL_1_1") (pintype "passive"))
    )
    (net (code "6") (name "/E1_RXC") (class "Default")
      (node (ref "R116") (pin "2") (pinfunction "2_2") (pintype "passive"))
      (node (ref "U9") (pin "33") (pinfunction "RX_CLK_33") (pintype "passive"))
    )
    (net (code "7") (name "/E1_RXD0") (class "Default")
      (node (ref "R117") (pin "2") (pinfunction "2_2") (pintype "passive"))
      (node (ref "U9") (pin "31") (pinfunction "RXD0_31") (pintype "passive"))
    )
    (net (code "8") (name "/E1_RXD1") (class "Default")
      (node (ref "R118") (pin "2") (pinfunction "2_2") (pintype "passive"))
      (node (ref "U9") (pin "30") (pinfunction "RXD1_30") (pintype "passive"))
    )
    (net (code "9") (name "/E1_RXD2") (class "Default")
      (node (ref "R119") (pin "2") (pinfunction "2_2") (pintype "passive"))
      (node (ref "U9") (pin "28") (pinfunction "RXD2_28") (pintype "passive"))
    )
    (net (code "10") (name "/E1_RXD3") (class "Default")
      (node (ref "R120") (pin "2") (pinfunction "2_2") (pintype "passive"))
      (node (ref "U9") (pin "27") (pinfunction "RXD3_27") (pintype "passive"))
    )
    (net (code "11") (name "/E1_RX_DV") (class "Default")
      (node (ref "R121") (pin "2") (pinfunction "2_2") (pintype "passive"))
      (node (ref "U9") (pin "32") (pinfunction "RX_DV_32") (pintype "passive"))
    )
    (net (code "12") (name "/ENET1_PHY_INT_B") (class "Default")
      (node (ref "R129") (pin "1") (pinfunction "1_1") (pintype "passive"))
    )
    (net (code "13") (name "/ENET1_PHY_RST_B") (class "Default")
      (node (ref "D8") (pin "1") (pinfunction "K_1") (pintype "passive"))
    )
    (net (code "14") (name "/ENET1_RGMII_RXC") (class "Default")
      (node (ref "R107") (pin "1") (pinfunction "1_1") (pintype "passive"))
      (node (ref "R114") (pin "2") (pinfunction "2_2") (pintype "passive"))
      (node (ref "R116") (pin "1") (pinfunction "1_1") (pintype "passive"))
    )
    (net (code "15") (name "/ENET1_RGMII_RXD0") (class "Default")
      (node (ref "R103") (pin "1") (pinfunction "1_1") (pintype "passive"))
      (node (ref "R109") (pin "2") (pinfunction "2_2") (pintype "passive"))
      (node (ref "R117") (pin "1") (pinfunction "1_1") (pintype "passive"))
    )
    (net (code "16") (name "/ENET1_RGMII_RXD1") (class "Default")
      (node (ref "R104") (pin "1") (pinfunction "1_1") (pintype "passive"))
      (node (ref "R110") (pin "2") (pinfunction "2_2") (pintype "passive"))
      (node (ref "R118") (pin "1") (pinfunction "1_1") (pintype "passive"))
    )
    (net (code "17") (name "/ENET1_RGMII_RXD2") (class "Default")
      (node (ref "R105") (pin "1") (pinfunction "1_1") (pintype "passive"))
      (node (ref "R111") (pin "2") (pinfunction "2_2") (pintype "passive"))
      (node (ref "R119") (pin "1") (pinfunction "1_1") (pintype "passive"))
    )
    (net (code "18") (name "/ENET1_RGMII_RXD3") (class "Default")
      (node (ref "R106") (pin "1") (pinfunction "1_1") (pintype "passive"))
      (node (ref "R113") (pin "2") (pinfunction "2_2") (pintype "passive"))
      (node (ref "R120") (pin "1") (pinfunction "1_1") (pintype "passive"))
    )
    (net (code "19") (name "/ENET1_RGMII_RX_CTL") (class "Default")
      (node (ref "R108") (pin "1") (pinfunction "1_1") (pintype "passive"))
      (node (ref "R115") (pin "2") (pinfunction "2_2") (pintype "passive"))
      (node (ref "R121") (pin "1") (pinfunction "1_1") (pintype "passive"))
    )
    (net (code "20") (name "/ENET1_RGMII_TXC") (class "Default")
      (node (ref "U9") (pin "35") (pinfunction "GTX_CLK_35") (pintype "passive"))
    )
    (net (code "21") (name "/ENET1_RGMII_TXD0") (class "Default")
      (node (ref "U9") (pin "36") (pinfunction "TXD0_36") (pintype "passive"))
    )
    (net (code "22") (name "/ENET1_RGMII_TXD1") (class "Default")
      (node (ref "U9") (pin "37") (pinfunction "TXD1_37") (pintype "passive"))
    )
    (net (code "23") (name "/ENET1_RGMII_TXD2") (class "Default")
      (node (ref "U9") (pin "38") (pinfunction "TXD2_38") (pintype "passive"))
    )
    (net (code "24") (name "/ENET1_RGMII_TXD3") (class "Default")
      (node (ref "U9") (pin "39") (pinfunction "TXD3_39") (pintype "passive"))
    )
    (net (code "25") (name "/ENET1_RGMII_TX_CTL") (class "Default")
      (node (ref "U9") (pin "34") (pinfunction "TX_EN_34") (pintype "passive"))
    )
    (net (code "26") (name "/ENET_PHY_MDC") (class "Default")
      (node (ref "U9") (pin "1") (pinfunction "MDC_1") (pintype "passive+no_connect"))
    )
    (net (code "27") (name "/ENET_PHY_MDIO") (class "Default")
      (node (ref "U9") (pin "48") (pinfunction "MDIO_48") (pintype "passive+no_connect"))
    )
    (net (code "28") (name "/ETH_TRX0_N") (class "Default")
      (node (ref "D5") (pin "2") (pinfunction "CH2_2") (pintype "passive"))
      (node (ref "D5") (pin "9") (pinfunction "NC3_9") (pintype "passive"))
      (node (ref "J12") (pin "10") (pinfunction "TRD1-_10") (pintype "passive"))
      (node (ref "U9") (pin "12") (pinfunction "TRXN0_12") (pintype "passive"))
    )
    (net (code "29") (name "/ETH_TRX0_P") (class "Default")
      (node (ref "D5") (pin "1") (pinfunction "CH1_1") (pintype "passive"))
      (node (ref "D5") (pin "10") (pinfunction "NC4_10") (pintype "passive"))
      (node (ref "J12") (pin "11") (pinfunction "TRD1+_11") (pintype "passive"))
      (node (ref "U9") (pin "11") (pinfunction "TRXP0_11") (pintype "passive"))
    )
    (net (code "30") (name "/ETH_TRX1_N") (class "Default")
      (node (ref "D5") (pin "5") (pinfunction "CH4_5") (pintype "passive"))
      (node (ref "D5") (pin "6") (pinfunction "NC1_6") (pintype "passive"))
      (node (ref "J12") (pin "5") (pinfunction "TRD2-_5") (pintype "passive"))
      (node (ref "U9") (pin "15") (pinfunction "TRXN1_15") (pintype "passive"))
    )
    (net (code "31") (name "/ETH_TRX1_P") (class "Default")
      (node (ref "D5") (pin "4") (pinfunction "CH3_4") (pintype "passive"))
      (node (ref "D5") (pin "7") (pinfunction "NC2_7") (pintype "passive"))
      (node (ref "J12") (pin "4") (pinfunction "TRD2+_4") (pintype "passive"))
      (node (ref "U9") (pin "14") (pinfunction "TRXP1_14") (pintype "passive"))
    )
    (net (code "32") (name "/ETH_TRX2_N") (class "Default")
      (node (ref "D6") (pin "2") (pinfunction "CH2_2") (pintype "passive"))
      (node (ref "D6") (pin "9") (pinfunction "NC3_9") (pintype "passive"))
      (node (ref "J12") (pin "2") (pinfunction "TRD3-_2") (pintype "passive"))
      (node (ref "U9") (pin "18") (pinfunction "TRXN2_18") (pintype "passive"))
    )
    (net (code "33") (name "/ETH_TRX2_P") (class "Default")
      (node (ref "D6") (pin "1") (pinfunction "CH1_1") (pintype "passive"))
      (node (ref "D6") (pin "10") (pinfunction "NC4_10") (pintype "passive"))
      (node (ref "J12") (pin "3") (pinfunction "TRD3+_3") (pintype "passive"))
      (node (ref "U9") (pin "17") (pinfunction "TRXP2_17") (pintype "passive"))
    )
    (net (code "34") (name "/ETH_TRX3_N") (class "Default")
      (node (ref "D6") (pin "5") (pinfunction "CH4_5") (pintype "passive"))
      (node (ref "D6") (pin "6") (pinfunction "NC1_6") (pintype "passive"))
      (node (ref "J12") (pin "9") (pinfunction "TRD4-_9") (pintype "passive"))
      (node (ref "U9") (pin "21") (pinfunction "TRXN3_21") (pintype "passive"))
    )
    (net (code "35") (name "/ETH_TRX3_P") (class "Default")
      (node (ref "D6") (pin "4") (pinfunction "CH3_4") (pintype "passive"))
      (node (ref "D6") (pin "7") (pinfunction "NC2_7") (pintype "passive"))
      (node (ref "J12") (pin "8") (pinfunction "TRD4+_8") (pintype "passive"))
      (node (ref "U9") (pin "20") (pinfunction "TRXP3_20") (pintype "passive"))
    )
    (net (code "36") (name "/LED_10_100") (class "Default")
      (node (ref "C272") (pin "2") (pinfunction "2_2") (pintype "passive"))
      (node (ref "R128") (pin "1") (pinfunction "1_1") (pintype "passive"))
      (node (ref "U9") (pin "26") (pinfunction "LED_LINK10_100_26") (pintype "passive"))
    )
    (net (code "37") (name "/LED_1000") (class "Default")
      (node (ref "C271") (pin "2") (pinfunction "2_2") (pintype "passive"))
      (node (ref "R126") (pin "1") (pinfunction "1_1") (pintype "passive"))
      (node (ref "R131") (pin "2") (pinfunction "2_2") (pintype "passive"))
      (node (ref "R132") (pin "1") (pinfunction "1_1") (pintype "passive"))
      (node (ref "R133") (pin "2") (pinfunction "2_2") (pintype "passive"))
      (node (ref "U9") (pin "24") (pinfunction "LED_LINK1000_24") (pintype "passive"))
    )
    (net (code "38") (name "/LED_ACT") (class "Default")
      (node (ref "C270") (pin "2") (pinfunction "2_2") (pintype "passive"))
      (node (ref "R127") (pin "1") (pinfunction "1_1") (pintype "passive"))
      (node (ref "R130") (pin "1") (pinfunction "1_1") (pintype "passive"))
      (node (ref "R134") (pin "2") (pinfunction "2_2") (pintype "passive"))
      (node (ref "U9") (pin "23") (pinfunction "LED_ACT_23") (pintype "passive"))
    )
    (net (code "39") (name "/LINKACT") (class "Default")
      (node (ref "J12") (pin "16") (pinfunction "16_16") (pintype "passive"))
      (node (ref "R130") (pin "2") (pinfunction "2_2") (pintype "passive"))
    )
    (net (code "40") (name "/SPD_10_100") (class "Default")
      (node (ref "J12") (pin "14") (pinfunction "14_14") (pintype "passive"))
      (node (ref "R128") (pin "2") (pinfunction "2_2") (pintype "passive"))
    )
    (net (code "42") (name "1V8") (class "Default")
      (node (ref "R123") (pin "2") (pinfunction "2_2") (pintype "passive"))
    )
    (net (code "43") (name "3V3") (class "Default")
      (node (ref "C254") (pin "2") (pinfunction "2_2") (pintype "passive"))
      (node (ref "C255") (pin "2") (pinfunction "2_2") (pintype "passive"))
      (node (ref "D7") (pin "1") (pinfunction "K_1") (pintype "passive"))
      (node (ref "L13") (pin "1") (pinfunction "1_1") (pintype "passive"))
      (node (ref "R122") (pin "2") (pinfunction "2_2") (pintype "passive"))
      (node (ref "R125") (pin "2") (pinfunction "2_2") (pintype "passive"))
      (node (ref "U9") (pin "4") (pinfunction "VDD33_4") (pintype "passive"))
    )
    (net (code "44") (name "ATH_AVDD33") (class "Default")
      (node (ref "C256") (pin "2") (pinfunction "2_2") (pintype "passive"))
      (node (ref "C257") (pin "2") (pinfunction "2_2") (pintype "passive"))
      (node (ref "L13") (pin "2") (pinfunction "2_2") (pintype "passive"))
      (node (ref "U9") (pin "16") (pinfunction "AVDD33_16") (pintype "passive"))
    )
    (net (code "45") (name "ATH_AVDDL") (class "Default")
      (node (ref "C263") (pin "2") (pinfunction "2_2") (pintype "passive"))
      (node (ref "C264") (pin "2") (pinfunction "2_2") (pintype "passive"))
      (node (ref "C265") (pin "2") (pinfunction "2_2") (pintype "passive"))
      (node (ref "C266") (pin "2") (pinfunction "2_2") (pintype "passive"))
      (node (ref "L15") (pin "2") (pinfunction "2_2") (pintype "passive"))
      (node (ref "U9") (pin "13") (pinfunction "AVDDL_2_13") (pintype "passive"))
      (node (ref "U9") (pin "19") (pinfunction "AVDDL_3_19") (pintype "passive"))
      (node (ref "U9") (pin "44") (pinfunction "AVDDL_4_44") (pintype "passive"))
      (node (ref "U9") (pin "8") (pinfunction "AVDDL_1_8") (pintype "passive"))
    )
    (net (code "46") (name "ATH_ENET1_VDDIO") (class "Default")
      (node (ref "C258") (pin "2") (pinfunction "2_2") (pintype "passive"))
      (node (ref "C259") (pin "2") (pinfunction "2_2") (pintype "passive"))
      (node (ref "R103") (pin "2") (pinfunction "2_2") (pintype "passive"))
      (node (ref "R104") (pin "2") (pinfunction "2_2") (pintype "passive"))
      (node (ref "R105") (pin "2") (pinfunction "2_2") (pintype "passive"))
      (node (ref "R106") (pin "2") (pinfunction "2_2") (pintype "passive"))
      (node (ref "R107") (pin "2") (pinfunction "2_2") (pintype "passive"))
      (node (ref "R108") (pin "2") (pinfunction "2_2") (pintype "passive"))
      (node (ref "R112") (pin "1") (pinfunction "1_1") (pintype "passive"))
    )
    (net (code "47") (name "ATH_PHY_DVDDL_1V1") (class "Default")
      (node (ref "C261") (pin "2") (pinfunction "2_2") (pintype "passive"))
      (node (ref "C262") (pin "2") (pinfunction "2_2") (pintype "passive"))
      (node (ref "L14") (pin "2") (pinfunction "2_2") (pintype "passive"))
      (node (ref "L15") (pin "1") (pinfunction "1_1") (pintype "passive"))
      (node (ref "R124") (pin "2") (pinfunction "2_2") (pintype "passive"))
      (node (ref "U9") (pin "47") (pinfunction "DVDDL_47") (pintype "passive"))
    )
    (net (code "48") (name "ATH_PHY_VDDH") (class "Default")
      (node (ref "C260") (pin "2") (pinfunction "2_2") (pintype "passive"))
      (node (ref "R112") (pin "2") (pinfunction "2_2") (pintype "passive"))
      (node (ref "R126") (pin "2") (pinfunction "2_2") (pintype "passive"))
      (node (ref "R127") (pin "2") (pinfunction "2_2") (pintype "passive"))
    )
    (net (code "49") (name "CHASIS") (class "Default")
      (node (ref "J12") (pin "S1") (pinfunction "SHIELD_S1") (pintype "passive"))
      (node (ref "J12") (pin "S2") (pinfunction "SHIELD_S2") (pintype "passive"))
    )
    (net (code "50") (name "GND") (class "Default")
      (node (ref "C254") (pin "1") (pinfunction "1_1") (pintype "passive"))
      (node (ref "C255") (pin "1") (pinfunction "1_1") (pintype "passive"))
      (node (ref "C256") (pin "1") (pinfunction "1_1") (pintype "passive"))
      (node (ref "C257") (pin "1") (pinfunction "1_1") (pintype "passive"))
      (node (ref "C258") (pin "1") (pinfunction "1_1") (pintype "passive"))
      (node (ref "C259") (pin "1") (pinfunction "1_1") (pintype "passive"))
      (node (ref "C260") (pin "1") (pinfunction "1_1") (pintype "passive"))
      (node (ref "C261") (pin "1") (pinfunction "1_1") (pintype "passive"))
      (node (ref "C262") (pin "1") (pinfunction "1_1") (pintype "passive"))
      (node (ref "C263") (pin "1") (pinfunction "1_1") (pintype "passive"))
      (node (ref "C264") (pin "1") (pinfunction "1_1") (pintype "passive"))
      (node (ref "C265") (pin "1") (pinfunction "1_1") (pintype "passive"))
      (node (ref "C266") (pin "1") (pinfunction "1_1") (pintype "passive"))
      (node (ref "C267") (pin "1") (pinfunction "1_1") (pintype "passive"))
      (node (ref "C268") (pin "1") (pinfunction "1_1") (pintype "passive"))
      (node (ref "C269") (pin "1") (pinfunction "1_1") (pintype "passive"))
      (node (ref "C270") (pin "1") (pinfunction "1_1") (pintype "passive"))
      (node (ref "C271") (pin "1") (pinfunction "1_1") (pintype "passive"))
      (node (ref "C272") (pin "1") (pinfunction "1_1") (pintype "passive"))
      (node (ref "C273") (pin "1") (pinfunction "1_1") (pintype "passive"))
      (node (ref "C274") (pin "1") (pinfunction "1_1") (pintype "passive"))
      (node (ref "D5") (pin "3") (pinfunction "GND1_3") (pintype "power_in"))
      (node (ref "D5") (pin "8") (pinfunction "GND2_8") (pintype "power_in"))
      (node (ref "D6") (pin "3") (pinfunction "GND1_3") (pintype "power_in"))
      (node (ref "D6") (pin "8") (pinfunction "GND2_8") (pintype "power_in"))
      (node (ref "D9") (pin "1") (pinfunction "C_1") (pintype "passive"))
      (node (ref "J12") (pin "13") (pinfunction "13_13") (pintype "passive"))
      (node (ref "J12") (pin "15") (pinfunction "15_15") (pintype "passive"))
      (node (ref "R109") (pin "1") (pinfunction "1_1") (pintype "passive"))
      (node (ref "R110") (pin "1") (pinfunction "1_1") (pintype "passive"))
      (node (ref "R111") (pin "1") (pinfunction "1_1") (pintype "passive"))
      (node (ref "R113") (pin "1") (pinfunction "1_1") (pintype "passive"))
      (node (ref "R114") (pin "1") (pinfunction "1_1") (pintype "passive"))
      (node (ref "R115") (pin "1") (pinfunction "1_1") (pintype "passive"))
      (node (ref "R131") (pin "1") (pinfunction "1_1") (pintype "passive"))
      (node (ref "R133") (pin "1") (pinfunction "1_1") (pintype "passive"))
      (node (ref "R134") (pin "1") (pinfunction "1_1") (pintype "passive"))
      (node (ref "R135") (pin "1") (pinfunction "1_1") (pintype "passive"))
      (node (ref "U9") (pin "49") (pinfunction "EP_(GND)_49") (pintype "passive"))
      (node (ref "Y3") (pin "2") (pinfunction "GND_1_2") (pintype "passive"))
      (node (ref "Y3") (pin "4") (pinfunction "GND_2_4") (pintype "passive"))
    )
    (net (code "51") (name "Net-(D7-A)") (class "Default")
      (node (ref "C268") (pin "2") (pinfunction "2_2") (pintype "passive"))
      (node (ref "C269") (pin "2") (pinfunction "2_2") (pintype "passive"))
      (node (ref "D7") (pin "2") (pinfunction "A_2") (pintype "passive"))
      (node (ref "D8") (pin "2") (pinfunction "A_2") (pintype "passive"))
      (node (ref "R125") (pin "1") (pinfunction "1_1") (pintype "passive"))
      (node (ref "U9") (pin "2") (pinfunction "RSTN_2") (pintype "passive"))
    )
    (net (code "52") (name "Net-(D9-A)") (class "Default")
      (node (ref "D9") (pin "2") (pinfunction "A_2") (pintype "passive"))
      (node (ref "R132") (pin "2") (pinfunction "2_2") (pintype "passive"))
    )
    (net (code "53") (name "Net-(J12-TRCT1)") (class "Default")
      (node (ref "C267") (pin "2") (pinfunction "2_2") (pintype "passive"))
      (node (ref "J12") (pin "1") (pinfunction "TRCT3_1") (pintype "passive"))
      (node (ref "J12") (pin "12") (pinfunction "TRCT1_12") (pintype "passive"))
      (node (ref "J12") (pin "6") (pinfunction "TRCT2_6") (pintype "passive"))
      (node (ref "J12") (pin "7") (pinfunction "TRCT4_7") (pintype "passive"))
    )
    (net (code "54") (name "Net-(U9-CLK_25M)") (class "Default")
      (node (ref "TP44") (pin "1") (pinfunction "1_1") (pintype "passive"))
      (node (ref "U9") (pin "25") (pinfunction "CLK_25M_25") (pintype "passive"))
    )
    (net (code "55") (name "Net-(U9-INT)") (class "Default")
      (node (ref "R123") (pin "1") (pinfunction "1_1") (pintype "passive"))
      (node (ref "R129") (pin "2") (pinfunction "2_2") (pintype "passive"))
      (node (ref "U9") (pin "5") (pinfunction "INT_5") (pintype "passive"))
    )
    (net (code "56") (name "Net-(U9-PPS)") (class "Default")
      (node (ref "TP43") (pin "1") (pinfunction "1_1") (pintype "passive"))
      (node (ref "U9") (pin "22") (pinfunction "PPS_22") (pintype "passive"))
    )
    (net (code "57") (name "Net-(U9-SD)") (class "Default")
      (node (ref "R124") (pin "1") (pinfunction "1_1") (pintype "passive"))
      (node (ref "U9") (pin "41") (pinfunction "SD_41") (pintype "passive"))
    )
    (net (code "58") (name "Net-(U9-WOL_INT)") (class "Default")
      (node (ref "R122") (pin "1") (pinfunction "1_1") (pintype "passive"))
      (node (ref "TP42") (pin "1") (pinfunction "1_1") (pintype "passive"))
      (node (ref "U9") (pin "40") (pinfunction "WOL_INT_40") (pintype "passive"))
    )
    (net (code "59") (name "unconnected-(U9-SIN-Pad45)") (class "Default")
      (node (ref "U9") (pin "45") (pinfunction "SIN_45") (pintype "passive+no_connect"))
    )
    (net (code "60") (name "unconnected-(U9-SIP-Pad46)") (class "Default")
      (node (ref "U9") (pin "46") (pinfunction "SIP_46") (pintype "passive+no_connect"))
    )
    (net (code "61") (name "unconnected-(U9-SON-Pad42)") (class "Default")
      (node (ref "U9") (pin "42") (pinfunction "SON_42") (pintype "passive+no_connect"))
    )
    (net (code "62") (name "unconnected-(U9-SOP-Pad43)") (class "Default")
      (node (ref "U9") (pin "43") (pinfunction "SOP_43") (pintype "passive+no_connect"))
    )
    (net (code "63") (name "unconnected-(U9-VDDH_REG-Pad10)") (class "Default")
      (node (ref "U9") (pin "10") (pinfunction "VDDH_REG_10") (pintype "passive"))
    )
    (net (code "64") (name "unconnected-(U9-VDDIO_REG-Pad29)") (class "Default")
      (node (ref "U9") (pin "29") (pinfunction "VDDIO_REG_29") (pintype "passive"))
    )
  )
)
